# Z7_POWER2.net
KiCad netlist of a schematic drawn in Altium Designer
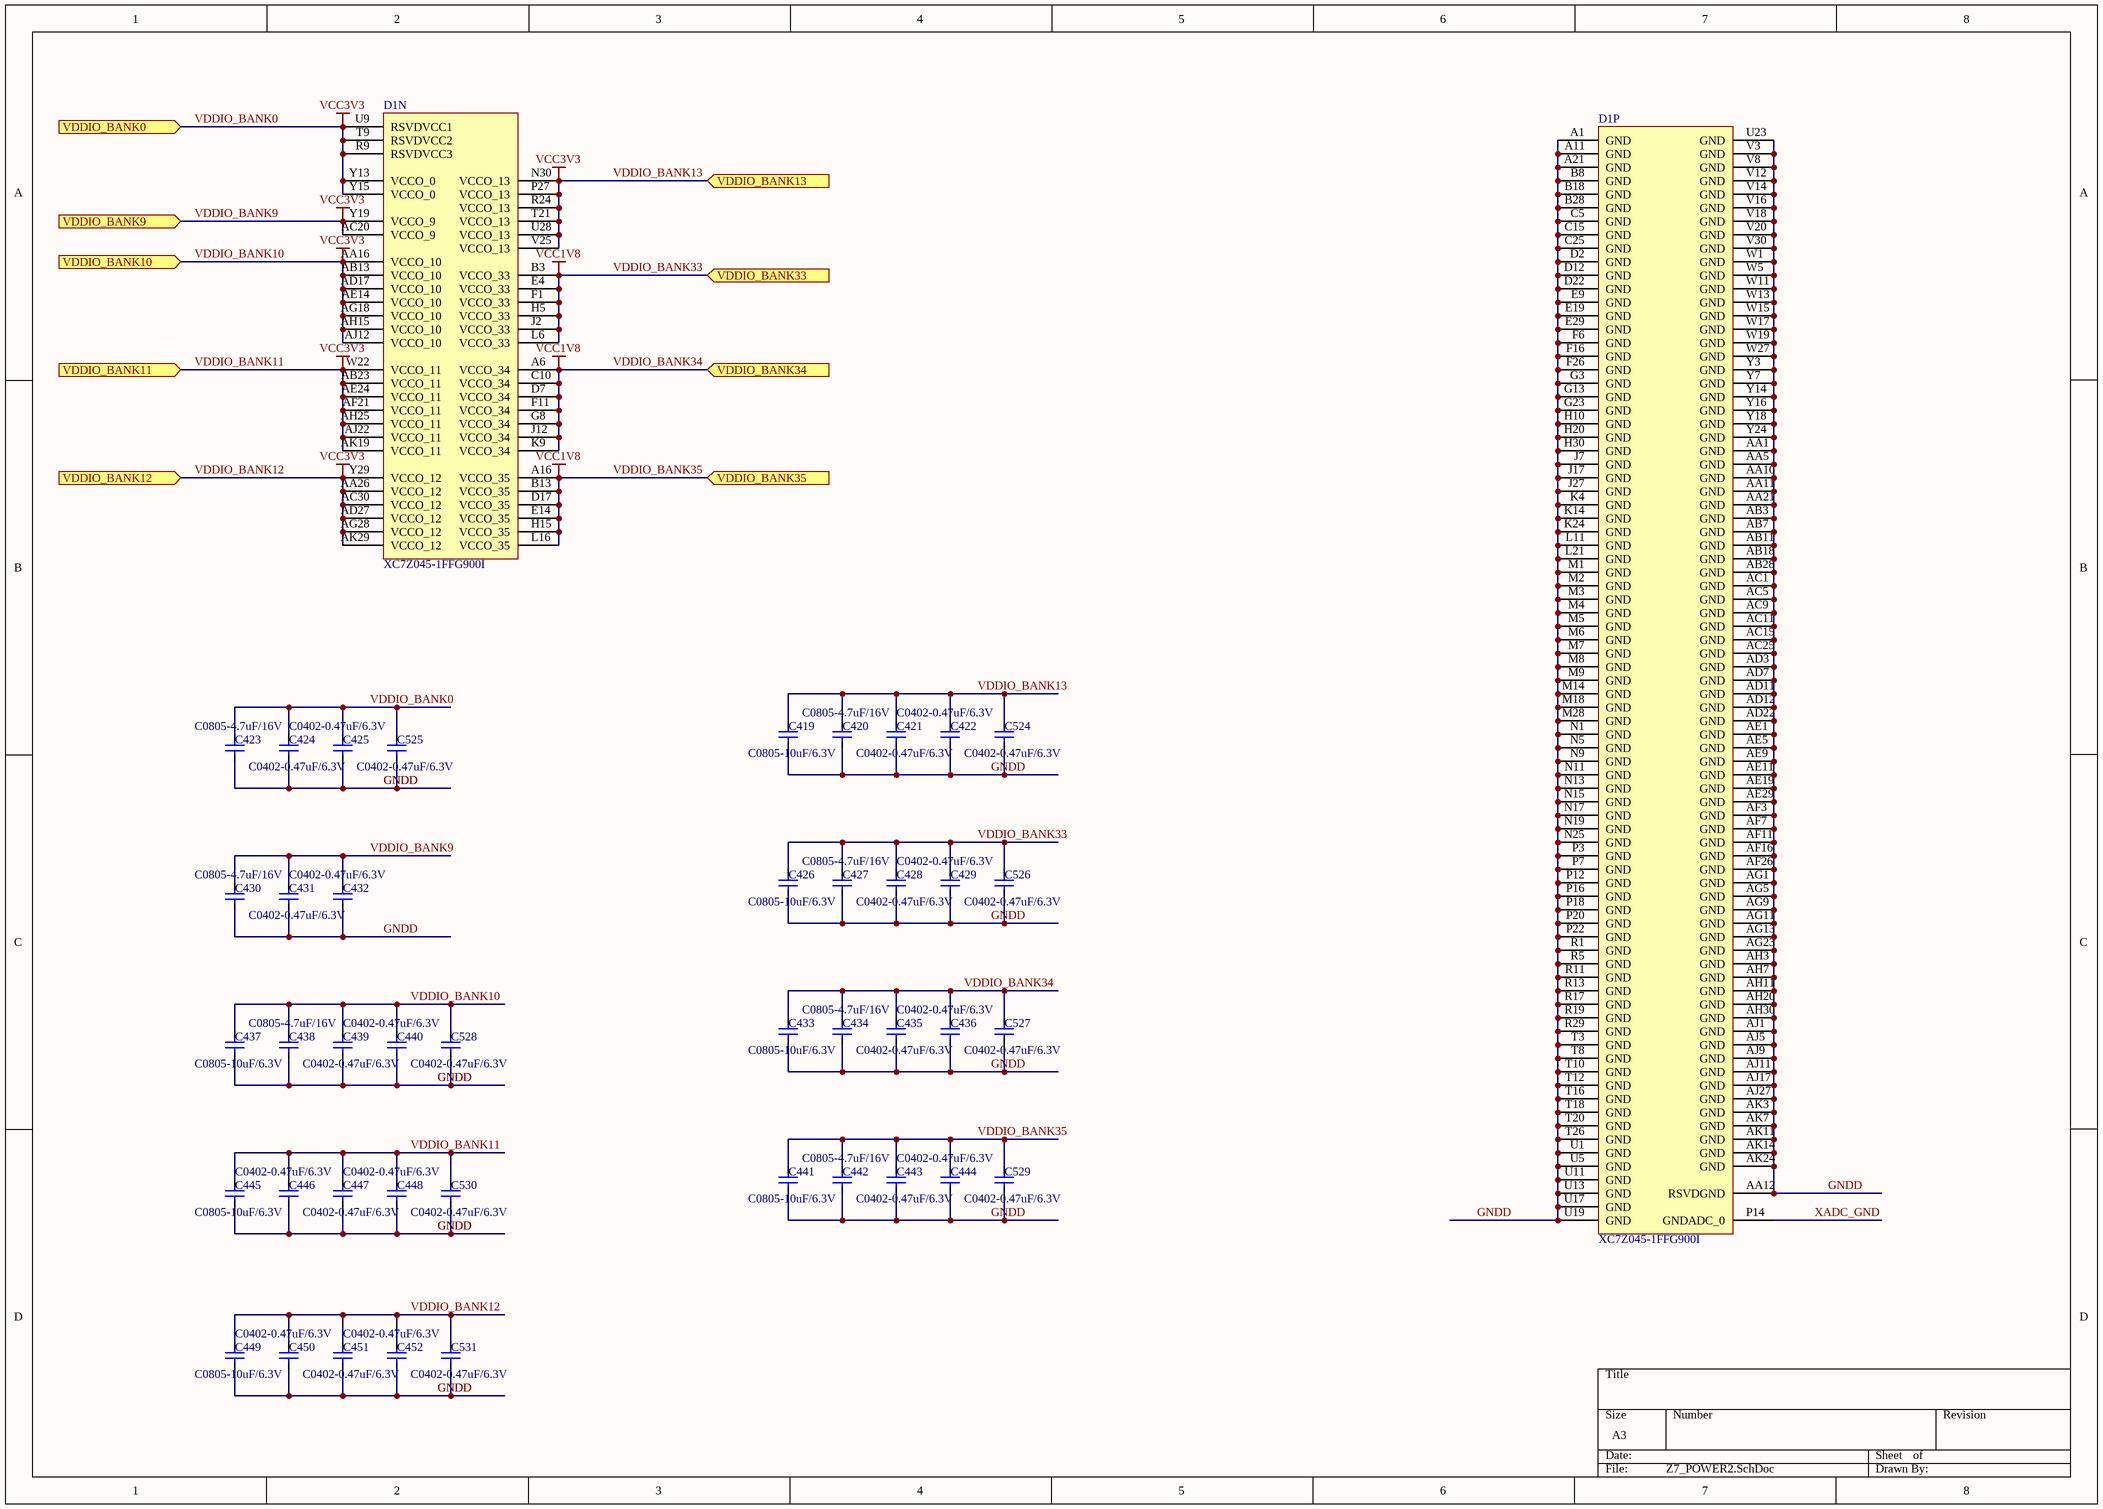
[diagram p0: Z7_POWER2.SchDoc]

(export (version "E")
  (design (tool "Eeschema 10.0.6"))
  (components
    (comp (ref "C419")
      (value "C0805-10uF/6.3V")
      (footprint "C0805")
      (fields (field (name "SCHEMATIC_PART") "CAP"))
      (libsource (lib "Database_Libs1") (part "CAP"))
    )
    (comp (ref "C420")
      (value "C0805-4.7uF/16V")
      (footprint "C0805")
      (description "X7R")
      (fields (field (name "SCHEMATIC_PART") "CAP") (field (name "MANUFACTURER") "SAMSUNG"))
      (libsource (lib "Database_Libs1") (part "CAP"))
    )
    (comp (ref "C421")
      (value "C0402-0.47uF/6.3V")
      (footprint "C0402")
      (description "X7R")
      (fields (field (name "SCHEMATIC_PART") "CAP") (field (name "MANUFACTURER") "SAMSUNG"))
      (libsource (lib "Database_Libs1") (part "CAP"))
    )
    (comp (ref "C422")
      (value "C0402-0.47uF/6.3V")
      (footprint "C0402")
      (description "X7R")
      (fields (field (name "SCHEMATIC_PART") "CAP") (field (name "MANUFACTURER") "SAMSUNG"))
      (libsource (lib "Database_Libs1") (part "CAP"))
    )
    (comp (ref "C423")
      (value "C0805-4.7uF/16V")
      (footprint "C0805")
      (description "X7R")
      (fields (field (name "SCHEMATIC_PART") "CAP") (field (name "MANUFACTURER") "SAMSUNG"))
      (libsource (lib "Database_Libs1") (part "CAP"))
    )
    (comp (ref "C424")
      (value "C0402-0.47uF/6.3V")
      (footprint "C0402")
      (description "X7R")
      (fields (field (name "SCHEMATIC_PART") "CAP") (field (name "MANUFACTURER") "SAMSUNG"))
      (libsource (lib "Database_Libs1") (part "CAP"))
    )
    (comp (ref "C425")
      (value "C0402-0.47uF/6.3V")
      (footprint "C0402")
      (description "X7R")
      (fields (field (name "SCHEMATIC_PART") "CAP") (field (name "MANUFACTURER") "SAMSUNG"))
      (libsource (lib "Database_Libs1") (part "CAP"))
    )
    (comp (ref "C426")
      (value "C0805-10uF/6.3V")
      (footprint "C0805")
      (fields (field (name "SCHEMATIC_PART") "CAP"))
      (libsource (lib "Database_Libs1") (part "CAP"))
    )
    (comp (ref "C427")
      (value "C0805-4.7uF/16V")
      (footprint "C0805")
      (description "X7R")
      (fields (field (name "SCHEMATIC_PART") "CAP") (field (name "MANUFACTURER") "SAMSUNG"))
      (libsource (lib "Database_Libs1") (part "CAP"))
    )
    (comp (ref "C428")
      (value "C0402-0.47uF/6.3V")
      (footprint "C0402")
      (description "X7R")
      (fields (field (name "SCHEMATIC_PART") "CAP") (field (name "MANUFACTURER") "SAMSUNG"))
      (libsource (lib "Database_Libs1") (part "CAP"))
    )
    (comp (ref "C429")
      (value "C0402-0.47uF/6.3V")
      (footprint "C0402")
      (description "X7R")
      (fields (field (name "SCHEMATIC_PART") "CAP") (field (name "MANUFACTURER") "SAMSUNG"))
      (libsource (lib "Database_Libs1") (part "CAP"))
    )
    (comp (ref "C430")
      (value "C0805-4.7uF/16V")
      (footprint "C0805")
      (description "X7R")
      (fields (field (name "SCHEMATIC_PART") "CAP") (field (name "MANUFACTURER") "SAMSUNG"))
      (libsource (lib "Database_Libs1") (part "CAP"))
    )
    (comp (ref "C431")
      (value "C0402-0.47uF/6.3V")
      (footprint "C0402")
      (description "X7R")
      (fields (field (name "SCHEMATIC_PART") "CAP") (field (name "MANUFACTURER") "SAMSUNG"))
      (libsource (lib "Database_Libs1") (part "CAP"))
    )
    (comp (ref "C432")
      (value "C0402-0.47uF/6.3V")
      (footprint "C0402")
      (description "X7R")
      (fields (field (name "SCHEMATIC_PART") "CAP") (field (name "MANUFACTURER") "SAMSUNG"))
      (libsource (lib "Database_Libs1") (part "CAP"))
    )
    (comp (ref "C433")
      (value "C0805-10uF/6.3V")
      (footprint "C0805")
      (fields (field (name "SCHEMATIC_PART") "CAP"))
      (libsource (lib "Database_Libs1") (part "CAP"))
    )
    (comp (ref "C434")
      (value "C0805-4.7uF/16V")
      (footprint "C0805")
      (description "X7R")
      (fields (field (name "SCHEMATIC_PART") "CAP") (field (name "MANUFACTURER") "SAMSUNG"))
      (libsource (lib "Database_Libs1") (part "CAP"))
    )
    (comp (ref "C435")
      (value "C0402-0.47uF/6.3V")
      (footprint "C0402")
      (description "X7R")
      (fields (field (name "SCHEMATIC_PART") "CAP") (field (name "MANUFACTURER") "SAMSUNG"))
      (libsource (lib "Database_Libs1") (part "CAP"))
    )
    (comp (ref "C436")
      (value "C0402-0.47uF/6.3V")
      (footprint "C0402")
      (description "X7R")
      (fields (field (name "SCHEMATIC_PART") "CAP") (field (name "MANUFACTURER") "SAMSUNG"))
      (libsource (lib "Database_Libs1") (part "CAP"))
    )
    (comp (ref "C437")
      (value "C0805-10uF/6.3V")
      (footprint "C0805")
      (fields (field (name "SCHEMATIC_PART") "CAP"))
      (libsource (lib "Database_Libs1") (part "CAP"))
    )
    (comp (ref "C438")
      (value "C0805-4.7uF/16V")
      (footprint "C0805")
      (description "X7R")
      (fields (field (name "SCHEMATIC_PART") "CAP") (field (name "MANUFACTURER") "SAMSUNG"))
      (libsource (lib "Database_Libs1") (part "CAP"))
    )
    (comp (ref "C439")
      (value "C0402-0.47uF/6.3V")
      (footprint "C0402")
      (description "X7R")
      (fields (field (name "SCHEMATIC_PART") "CAP") (field (name "MANUFACTURER") "SAMSUNG"))
      (libsource (lib "Database_Libs1") (part "CAP"))
    )
    (comp (ref "C440")
      (value "C0402-0.47uF/6.3V")
      (footprint "C0402")
      (description "X7R")
      (fields (field (name "SCHEMATIC_PART") "CAP") (field (name "MANUFACTURER") "SAMSUNG"))
      (libsource (lib "Database_Libs1") (part "CAP"))
    )
    (comp (ref "C441")
      (value "C0805-10uF/6.3V")
      (footprint "C0805")
      (fields (field (name "SCHEMATIC_PART") "CAP"))
      (libsource (lib "Database_Libs1") (part "CAP"))
    )
    (comp (ref "C442")
      (value "C0805-4.7uF/16V")
      (footprint "C0805")
      (description "X7R")
      (fields (field (name "SCHEMATIC_PART") "CAP") (field (name "MANUFACTURER") "SAMSUNG"))
      (libsource (lib "Database_Libs1") (part "CAP"))
    )
    (comp (ref "C443")
      (value "C0402-0.47uF/6.3V")
      (footprint "C0402")
      (description "X7R")
      (fields (field (name "SCHEMATIC_PART") "CAP") (field (name "MANUFACTURER") "SAMSUNG"))
      (libsource (lib "Database_Libs1") (part "CAP"))
    )
    (comp (ref "C444")
      (value "C0402-0.47uF/6.3V")
      (footprint "C0402")
      (description "X7R")
      (fields (field (name "SCHEMATIC_PART") "CAP") (field (name "MANUFACTURER") "SAMSUNG"))
      (libsource (lib "Database_Libs1") (part "CAP"))
    )
    (comp (ref "C445")
      (value "C0805-10uF/6.3V")
      (footprint "C0805")
      (fields (field (name "SCHEMATIC_PART") "CAP"))
      (libsource (lib "Database_Libs1") (part "CAP"))
    )
    (comp (ref "C446")
      (value "C0402-0.47uF/6.3V")
      (footprint "C0402")
      (description "X7R")
      (fields (field (name "SCHEMATIC_PART") "CAP") (field (name "MANUFACTURER") "SAMSUNG"))
      (libsource (lib "Database_Libs1") (part "CAP"))
    )
    (comp (ref "C447")
      (value "C0402-0.47uF/6.3V")
      (footprint "C0402")
      (description "X7R")
      (fields (field (name "SCHEMATIC_PART") "CAP") (field (name "MANUFACTURER") "SAMSUNG"))
      (libsource (lib "Database_Libs1") (part "CAP"))
    )
    (comp (ref "C448")
      (value "C0402-0.47uF/6.3V")
      (footprint "C0402")
      (description "X7R")
      (fields (field (name "SCHEMATIC_PART") "CAP") (field (name "MANUFACTURER") "SAMSUNG"))
      (libsource (lib "Database_Libs1") (part "CAP"))
    )
    (comp (ref "C449")
      (value "C0805-10uF/6.3V")
      (footprint "C0805")
      (fields (field (name "SCHEMATIC_PART") "CAP"))
      (libsource (lib "Database_Libs1") (part "CAP"))
    )
    (comp (ref "C450")
      (value "C0402-0.47uF/6.3V")
      (footprint "C0402")
      (description "X7R")
      (fields (field (name "SCHEMATIC_PART") "CAP") (field (name "MANUFACTURER") "SAMSUNG"))
      (libsource (lib "Database_Libs1") (part "CAP"))
    )
    (comp (ref "C451")
      (value "C0402-0.47uF/6.3V")
      (footprint "C0402")
      (description "X7R")
      (fields (field (name "SCHEMATIC_PART") "CAP") (field (name "MANUFACTURER") "SAMSUNG"))
      (libsource (lib "Database_Libs1") (part "CAP"))
    )
    (comp (ref "C452")
      (value "C0402-0.47uF/6.3V")
      (footprint "C0402")
      (description "X7R")
      (fields (field (name "SCHEMATIC_PART") "CAP") (field (name "MANUFACTURER") "SAMSUNG"))
      (libsource (lib "Database_Libs1") (part "CAP"))
    )
    (comp (ref "C524")
      (value "C0402-0.47uF/6.3V")
      (footprint "C0402")
      (description "X7R")
      (fields (field (name "SCHEMATIC_PART") "CAP") (field (name "MANUFACTURER") "SAMSUNG"))
      (libsource (lib "Database_Libs1") (part "CAP"))
    )
    (comp (ref "C525")
      (value "C0402-0.47uF/6.3V")
      (footprint "C0402")
      (description "X7R")
      (fields (field (name "SCHEMATIC_PART") "CAP") (field (name "MANUFACTURER") "SAMSUNG"))
      (libsource (lib "Database_Libs1") (part "CAP"))
    )
    (comp (ref "C526")
      (value "C0402-0.47uF/6.3V")
      (footprint "C0402")
      (description "X7R")
      (fields (field (name "SCHEMATIC_PART") "CAP") (field (name "MANUFACTURER") "SAMSUNG"))
      (libsource (lib "Database_Libs1") (part "CAP"))
    )
    (comp (ref "C527")
      (value "C0402-0.47uF/6.3V")
      (footprint "C0402")
      (description "X7R")
      (fields (field (name "SCHEMATIC_PART") "CAP") (field (name "MANUFACTURER") "SAMSUNG"))
      (libsource (lib "Database_Libs1") (part "CAP"))
    )
    (comp (ref "C528")
      (value "C0402-0.47uF/6.3V")
      (footprint "C0402")
      (description "X7R")
      (fields (field (name "SCHEMATIC_PART") "CAP") (field (name "MANUFACTURER") "SAMSUNG"))
      (libsource (lib "Database_Libs1") (part "CAP"))
    )
    (comp (ref "C529")
      (value "C0402-0.47uF/6.3V")
      (footprint "C0402")
      (description "X7R")
      (fields (field (name "SCHEMATIC_PART") "CAP") (field (name "MANUFACTURER") "SAMSUNG"))
      (libsource (lib "Database_Libs1") (part "CAP"))
    )
    (comp (ref "C530")
      (value "C0402-0.47uF/6.3V")
      (footprint "C0402")
      (description "X7R")
      (fields (field (name "SCHEMATIC_PART") "CAP") (field (name "MANUFACTURER") "SAMSUNG"))
      (libsource (lib "Database_Libs1") (part "CAP"))
    )
    (comp (ref "C531")
      (value "C0402-0.47uF/6.3V")
      (footprint "C0402")
      (description "X7R")
      (fields (field (name "SCHEMATIC_PART") "CAP") (field (name "MANUFACTURER") "SAMSUNG"))
      (libsource (lib "Database_Libs1") (part "CAP"))
    )
    (comp (ref "D1")
      (value "XC7Z045-1FFG900I")
      (footprint "FFG900")
      (fields (field (name "GENERIC PART NUMBER") "XC7Z045") (field (name "MANUFACTURER") "Xilinx"))
      (libsource (lib "Xilinx Zynq-7000") (part "XC7Z045-1FFG900I"))
    )
  )
  (nets
    (net (code "1") (name "/GNDD") (class "Default")
      (node (ref "C419") (pin "2") (pinfunction "2_2") (pintype "passive"))
      (node (ref "C420") (pin "2") (pinfunction "2_2") (pintype "passive"))
      (node (ref "C421") (pin "2") (pinfunction "2_2") (pintype "passive"))
      (node (ref "C422") (pin "2") (pinfunction "2_2") (pintype "passive"))
      (node (ref "C423") (pin "2") (pinfunction "2_2") (pintype "passive"))
      (node (ref "C424") (pin "2") (pinfunction "2_2") (pintype "passive"))
      (node (ref "C425") (pin "2") (pinfunction "2_2") (pintype "passive"))
      (node (ref "C426") (pin "2") (pinfunction "2_2") (pintype "passive"))
      (node (ref "C427") (pin "2") (pinfunction "2_2") (pintype "passive"))
      (node (ref "C428") (pin "2") (pinfunction "2_2") (pintype "passive"))
      (node (ref "C429") (pin "2") (pinfunction "2_2") (pintype "passive"))
      (node (ref "C430") (pin "2") (pinfunction "2_2") (pintype "passive"))
      (node (ref "C431") (pin "2") (pinfunction "2_2") (pintype "passive"))
      (node (ref "C432") (pin "2") (pinfunction "2_2") (pintype "passive"))
      (node (ref "C433") (pin "2") (pinfunction "2_2") (pintype "passive"))
      (node (ref "C434") (pin "2") (pinfunction "2_2") (pintype "passive"))
      (node (ref "C435") (pin "2") (pinfunction "2_2") (pintype "passive"))
      (node (ref "C436") (pin "2") (pinfunction "2_2") (pintype "passive"))
      (node (ref "C437") (pin "2") (pinfunction "2_2") (pintype "passive"))
      (node (ref "C438") (pin "2") (pinfunction "2_2") (pintype "passive"))
      (node (ref "C439") (pin "2") (pinfunction "2_2") (pintype "passive"))
      (node (ref "C440") (pin "2") (pinfunction "2_2") (pintype "passive"))
      (node (ref "C441") (pin "2") (pinfunction "2_2") (pintype "passive"))
      (node (ref "C442") (pin "2") (pinfunction "2_2") (pintype "passive"))
      (node (ref "C443") (pin "2") (pinfunction "2_2") (pintype "passive"))
      (node (ref "C444") (pin "2") (pinfunction "2_2") (pintype "passive"))
      (node (ref "C445") (pin "2") (pinfunction "2_2") (pintype "passive"))
      (node (ref "C446") (pin "2") (pinfunction "2_2") (pintype "passive"))
      (node (ref "C447") (pin "2") (pinfunction "2_2") (pintype "passive"))
      (node (ref "C448") (pin "2") (pinfunction "2_2") (pintype "passive"))
      (node (ref "C449") (pin "2") (pinfunction "2_2") (pintype "passive"))
      (node (ref "C450") (pin "2") (pinfunction "2_2") (pintype "passive"))
      (node (ref "C451") (pin "2") (pinfunction "2_2") (pintype "passive"))
      (node (ref "C452") (pin "2") (pinfunction "2_2") (pintype "passive"))
      (node (ref "C524") (pin "2") (pinfunction "2_2") (pintype "passive"))
      (node (ref "C525") (pin "2") (pinfunction "2_2") (pintype "passive"))
      (node (ref "C526") (pin "2") (pinfunction "2_2") (pintype "passive"))
      (node (ref "C527") (pin "2") (pinfunction "2_2") (pintype "passive"))
      (node (ref "C528") (pin "2") (pinfunction "2_2") (pintype "passive"))
      (node (ref "C529") (pin "2") (pinfunction "2_2") (pintype "passive"))
      (node (ref "C530") (pin "2") (pinfunction "2_2") (pintype "passive"))
      (node (ref "C531") (pin "2") (pinfunction "2_2") (pintype "passive"))
      (node (ref "D1") (pin "A1") (pinfunction "GND_A1") (pintype "power_in"))
      (node (ref "D1") (pin "A11") (pinfunction "GND_A11") (pintype "power_in"))
      (node (ref "D1") (pin "A21") (pinfunction "GND_A21") (pintype "power_in"))
      (node (ref "D1") (pin "AA1") (pinfunction "GND_AA1") (pintype "power_in"))
      (node (ref "D1") (pin "AA10") (pinfunction "GND_AA10") (pintype "power_in"))
      (node (ref "D1") (pin "AA11") (pinfunction "GND_AA11") (pintype "power_in"))
      (node (ref "D1") (pin "AA12") (pinfunction "RSVDGND_AA12") (pintype "power_in"))
      (node (ref "D1") (pin "AA21") (pinfunction "GND_AA21") (pintype "power_in"))
      (node (ref "D1") (pin "AA5") (pinfunction "GND_AA5") (pintype "power_in"))
      (node (ref "D1") (pin "AB11") (pinfunction "GND_AB11") (pintype "power_in"))
      (node (ref "D1") (pin "AB18") (pinfunction "GND_AB18") (pintype "power_in"))
      (node (ref "D1") (pin "AB28") (pinfunction "GND_AB28") (pintype "power_in"))
      (node (ref "D1") (pin "AB3") (pinfunction "GND_AB3") (pintype "power_in"))
      (node (ref "D1") (pin "AB7") (pinfunction "GND_AB7") (pintype "power_in"))
      (node (ref "D1") (pin "AC1") (pinfunction "GND_AC1") (pintype "power_in"))
      (node (ref "D1") (pin "AC11") (pinfunction "GND_AC11") (pintype "power_in"))
      (node (ref "D1") (pin "AC15") (pinfunction "GND_AC15") (pintype "power_in"))
      (node (ref "D1") (pin "AC25") (pinfunction "GND_AC25") (pintype "power_in"))
      (node (ref "D1") (pin "AC5") (pinfunction "GND_AC5") (pintype "power_in"))
      (node (ref "D1") (pin "AC9") (pinfunction "GND_AC9") (pintype "power_in"))
      (node (ref "D1") (pin "AD11") (pinfunction "GND_AD11") (pintype "power_in"))
      (node (ref "D1") (pin "AD12") (pinfunction "GND_AD12") (pintype "power_in"))
      (node (ref "D1") (pin "AD22") (pinfunction "GND_AD22") (pintype "power_in"))
      (node (ref "D1") (pin "AD3") (pinfunction "GND_AD3") (pintype "power_in"))
      (node (ref "D1") (pin "AD7") (pinfunction "GND_AD7") (pintype "power_in"))
      (node (ref "D1") (pin "AE1") (pinfunction "GND_AE1") (pintype "power_in"))
      (node (ref "D1") (pin "AE11") (pinfunction "GND_AE11") (pintype "power_in"))
      (node (ref "D1") (pin "AE19") (pinfunction "GND_AE19") (pintype "power_in"))
      (node (ref "D1") (pin "AE29") (pinfunction "GND_AE29") (pintype "power_in"))
      (node (ref "D1") (pin "AE5") (pinfunction "GND_AE5") (pintype "power_in"))
      (node (ref "D1") (pin "AE9") (pinfunction "GND_AE9") (pintype "power_in"))
      (node (ref "D1") (pin "AF11") (pinfunction "GND_AF11") (pintype "power_in"))
      (node (ref "D1") (pin "AF16") (pinfunction "GND_AF16") (pintype "power_in"))
      (node (ref "D1") (pin "AF26") (pinfunction "GND_AF26") (pintype "power_in"))
      (node (ref "D1") (pin "AF3") (pinfunction "GND_AF3") (pintype "power_in"))
      (node (ref "D1") (pin "AF7") (pinfunction "GND_AF7") (pintype "power_in"))
      (node (ref "D1") (pin "AG1") (pinfunction "GND_AG1") (pintype "power_in"))
      (node (ref "D1") (pin "AG11") (pinfunction "GND_AG11") (pintype "power_in"))
      (node (ref "D1") (pin "AG13") (pinfunction "GND_AG13") (pintype "power_in"))
      (node (ref "D1") (pin "AG23") (pinfunction "GND_AG23") (pintype "power_in"))
      (node (ref "D1") (pin "AG5") (pinfunction "GND_AG5") (pintype "power_in"))
      (node (ref "D1") (pin "AG9") (pinfunction "GND_AG9") (pintype "power_in"))
      (node (ref "D1") (pin "AH11") (pinfunction "GND_AH11") (pintype "power_in"))
      (node (ref "D1") (pin "AH20") (pinfunction "GND_AH20") (pintype "power_in"))
      (node (ref "D1") (pin "AH3") (pinfunction "GND_AH3") (pintype "power_in"))
      (node (ref "D1") (pin "AH30") (pinfunction "GND_AH30") (pintype "power_in"))
      (node (ref "D1") (pin "AH7") (pinfunction "GND_AH7") (pintype "power_in"))
      (node (ref "D1") (pin "AJ1") (pinfunction "GND_AJ1") (pintype "power_in"))
      (node (ref "D1") (pin "AJ11") (pinfunction "GND_AJ11") (pintype "power_in"))
      (node (ref "D1") (pin "AJ17") (pinfunction "GND_AJ17") (pintype "power_in"))
      (node (ref "D1") (pin "AJ27") (pinfunction "GND_AJ27") (pintype "power_in"))
      (node (ref "D1") (pin "AJ5") (pinfunction "GND_AJ5") (pintype "power_in"))
      (node (ref "D1") (pin "AJ9") (pinfunction "GND_AJ9") (pintype "power_in"))
      (node (ref "D1") (pin "AK11") (pinfunction "GND_AK11") (pintype "power_in"))
      (node (ref "D1") (pin "AK14") (pinfunction "GND_AK14") (pintype "power_in"))
      (node (ref "D1") (pin "AK24") (pinfunction "GND_AK24") (pintype "power_in"))
      (node (ref "D1") (pin "AK3") (pinfunction "GND_AK3") (pintype "power_in"))
      (node (ref "D1") (pin "AK7") (pinfunction "GND_AK7") (pintype "power_in"))
      (node (ref "D1") (pin "B18") (pinfunction "GND_B18") (pintype "power_in"))
      (node (ref "D1") (pin "B28") (pinfunction "GND_B28") (pintype "power_in"))
      (node (ref "D1") (pin "B8") (pinfunction "GND_B8") (pintype "power_in"))
      (node (ref "D1") (pin "C15") (pinfunction "GND_C15") (pintype "power_in"))
      (node (ref "D1") (pin "C25") (pinfunction "GND_C25") (pintype "power_in"))
      (node (ref "D1") (pin "C5") (pinfunction "GND_C5") (pintype "power_in"))
      (node (ref "D1") (pin "D12") (pinfunction "GND_D12") (pintype "power_in"))
      (node (ref "D1") (pin "D2") (pinfunction "GND_D2") (pintype "power_in"))
      (node (ref "D1") (pin "D22") (pinfunction "GND_D22") (pintype "power_in"))
      (node (ref "D1") (pin "E19") (pinfunction "GND_E19") (pintype "power_in"))
      (node (ref "D1") (pin "E29") (pinfunction "GND_E29") (pintype "power_in"))
      (node (ref "D1") (pin "E9") (pinfunction "GND_E9") (pintype "power_in"))
      (node (ref "D1") (pin "F16") (pinfunction "GND_F16") (pintype "power_in"))
      (node (ref "D1") (pin "F26") (pinfunction "GND_F26") (pintype "power_in"))
      (node (ref "D1") (pin "F6") (pinfunction "GND_F6") (pintype "power_in"))
      (node (ref "D1") (pin "G13") (pinfunction "GND_G13") (pintype "power_in"))
      (node (ref "D1") (pin "G23") (pinfunction "GND_G23") (pintype "power_in"))
      (node (ref "D1") (pin "G3") (pinfunction "GND_G3") (pintype "power_in"))
      (node (ref "D1") (pin "H10") (pinfunction "GND_H10") (pintype "power_in"))
      (node (ref "D1") (pin "H20") (pinfunction "GND_H20") (pintype "power_in"))
      (node (ref "D1") (pin "H30") (pinfunction "GND_H30") (pintype "power_in"))
      (node (ref "D1") (pin "J17") (pinfunction "GND_J17") (pintype "power_in"))
      (node (ref "D1") (pin "J27") (pinfunction "GND_J27") (pintype "power_in"))
      (node (ref "D1") (pin "J7") (pinfunction "GND_J7") (pintype "power_in"))
      (node (ref "D1") (pin "K14") (pinfunction "GND_K14") (pintype "power_in"))
      (node (ref "D1") (pin "K24") (pinfunction "GND_K24") (pintype "power_in"))
      (node (ref "D1") (pin "K4") (pinfunction "GND_K4") (pintype "power_in"))
      (node (ref "D1") (pin "L11") (pinfunction "GND_L11") (pintype "power_in"))
      (node (ref "D1") (pin "L21") (pinfunction "GND_L21") (pintype "power_in"))
      (node (ref "D1") (pin "M1") (pinfunction "GND_M1") (pintype "power_in"))
      (node (ref "D1") (pin "M14") (pinfunction "GND_M14") (pintype "power_in"))
      (node (ref "D1") (pin "M18") (pinfunction "GND_M18") (pintype "power_in"))
      (node (ref "D1") (pin "M2") (pinfunction "GND_M2") (pintype "power_in"))
      (node (ref "D1") (pin "M28") (pinfunction "GND_M28") (pintype "power_in"))
      (node (ref "D1") (pin "M3") (pinfunction "GND_M3") (pintype "power_in"))
      (node (ref "D1") (pin "M4") (pinfunction "GND_M4") (pintype "power_in"))
      (node (ref "D1") (pin "M5") (pinfunction "GND_M5") (pintype "power_in"))
      (node (ref "D1") (pin "M6") (pinfunction "GND_M6") (pintype "power_in"))
      (node (ref "D1") (pin "M7") (pinfunction "GND_M7") (pintype "power_in"))
      (node (ref "D1") (pin "M8") (pinfunction "GND_M8") (pintype "power_in"))
      (node (ref "D1") (pin "M9") (pinfunction "GND_M9") (pintype "power_in"))
      (node (ref "D1") (pin "N1") (pinfunction "GND_N1") (pintype "power_in"))
      (node (ref "D1") (pin "N11") (pinfunction "GND_N11") (pintype "power_in"))
      (node (ref "D1") (pin "N13") (pinfunction "GND_N13") (pintype "power_in"))
      (node (ref "D1") (pin "N15") (pinfunction "GND_N15") (pintype "power_in"))
      (node (ref "D1") (pin "N17") (pinfunction "GND_N17") (pintype "power_in"))
      (node (ref "D1") (pin "N19") (pinfunction "GND_N19") (pintype "power_in"))
      (node (ref "D1") (pin "N25") (pinfunction "GND_N25") (pintype "power_in"))
      (node (ref "D1") (pin "N5") (pinfunction "GND_N5") (pintype "power_in"))
      (node (ref "D1") (pin "N9") (pinfunction "GND_N9") (pintype "power_in"))
      (node (ref "D1") (pin "P12") (pinfunction "GND_P12") (pintype "power_in"))
      (node (ref "D1") (pin "P16") (pinfunction "GND_P16") (pintype "power_in"))
      (node (ref "D1") (pin "P18") (pinfunction "GND_P18") (pintype "power_in"))
      (node (ref "D1") (pin "P20") (pinfunction "GND_P20") (pintype "power_in"))
      (node (ref "D1") (pin "P22") (pinfunction "GND_P22") (pintype "power_in"))
      (node (ref "D1") (pin "P3") (pinfunction "GND_P3") (pintype "power_in"))
      (node (ref "D1") (pin "P7") (pinfunction "GND_P7") (pintype "power_in"))
      (node (ref "D1") (pin "R1") (pinfunction "GND_R1") (pintype "power_in"))
      (node (ref "D1") (pin "R11") (pinfunction "GND_R11") (pintype "power_in"))
      (node (ref "D1") (pin "R13") (pinfunction "GND_R13") (pintype "power_in"))
      (node (ref "D1") (pin "R17") (pinfunction "GND_R17") (pintype "power_in"))
      (node (ref "D1") (pin "R19") (pinfunction "GND_R19") (pintype "power_in"))
      (node (ref "D1") (pin "R29") (pinfunction "GND_R29") (pintype "power_in"))
      (node (ref "D1") (pin "R5") (pinfunction "GND_R5") (pintype "power_in"))
      (node (ref "D1") (pin "T10") (pinfunction "GND_T10") (pintype "power_in"))
      (node (ref "D1") (pin "T12") (pinfunction "GND_T12") (pintype "power_in"))
      (node (ref "D1") (pin "T16") (pinfunction "GND_T16") (pintype "power_in"))
      (node (ref "D1") (pin "T18") (pinfunction "GND_T18") (pintype "power_in"))
      (node (ref "D1") (pin "T20") (pinfunction "GND_T20") (pintype "power_in"))
      (node (ref "D1") (pin "T26") (pinfunction "GND_T26") (pintype "power_in"))
      (node (ref "D1") (pin "T3") (pinfunction "GND_T3") (pintype "power_in"))
      (node (ref "D1") (pin "T8") (pinfunction "GND_T8") (pintype "power_in"))
      (node (ref "D1") (pin "U1") (pinfunction "GND_U1") (pintype "power_in"))
      (node (ref "D1") (pin "U11") (pinfunction "GND_U11") (pintype "power_in"))
      (node (ref "D1") (pin "U13") (pinfunction "GND_U13") (pintype "power_in"))
      (node (ref "D1") (pin "U17") (pinfunction "GND_U17") (pintype "power_in"))
      (node (ref "D1") (pin "U19") (pinfunction "GND_U19") (pintype "power_in"))
      (node (ref "D1") (pin "U23") (pinfunction "GND_U23") (pintype "power_in"))
      (node (ref "D1") (pin "U5") (pinfunction "GND_U5") (pintype "power_in"))
      (node (ref "D1") (pin "V12") (pinfunction "GND_V12") (pintype "power_in"))
      (node (ref "D1") (pin "V14") (pinfunction "GND_V14") (pintype "power_in"))
      (node (ref "D1") (pin "V16") (pinfunction "GND_V16") (pintype "power_in"))
      (node (ref "D1") (pin "V18") (pinfunction "GND_V18") (pintype "power_in"))
      (node (ref "D1") (pin "V20") (pinfunction "GND_V20") (pintype "power_in"))
      (node (ref "D1") (pin "V3") (pinfunction "GND_V3") (pintype "power_in"))
      (node (ref "D1") (pin "V30") (pinfunction "GND_V30") (pintype "power_in"))
      (node (ref "D1") (pin "V8") (pinfunction "GND_V8") (pintype "power_in"))
      (node (ref "D1") (pin "W1") (pinfunction "GND_W1") (pintype "power_in"))
      (node (ref "D1") (pin "W11") (pinfunction "GND_W11") (pintype "power_in"))
      (node (ref "D1") (pin "W13") (pinfunction "GND_W13") (pintype "power_in"))
      (node (ref "D1") (pin "W15") (pinfunction "GND_W15") (pintype "power_in"))
      (node (ref "D1") (pin "W17") (pinfunction "GND_W17") (pintype "power_in"))
      (node (ref "D1") (pin "W19") (pinfunction "GND_W19") (pintype "power_in"))
      (node (ref "D1") (pin "W27") (pinfunction "GND_W27") (pintype "power_in"))
      (node (ref "D1") (pin "W5") (pinfunction "GND_W5") (pintype "power_in"))
      (node (ref "D1") (pin "Y14") (pinfunction "GND_Y14") (pintype "power_in"))
      (node (ref "D1") (pin "Y16") (pinfunction "GND_Y16") (pintype "power_in"))
      (node (ref "D1") (pin "Y18") (pinfunction "GND_Y18") (pintype "power_in"))
      (node (ref "D1") (pin "Y24") (pinfunction "GND_Y24") (pintype "power_in"))
      (node (ref "D1") (pin "Y3") (pinfunction "GND_Y3") (pintype "power_in"))
      (node (ref "D1") (pin "Y7") (pinfunction "GND_Y7") (pintype "power_in"))
    )
    (net (code "2") (name "/XADC_GND") (class "Default")
      (node (ref "D1") (pin "P14") (pinfunction "GNDADC_0_P14") (pintype "power_in"))
    )
    (net (code "3") (name "VCC1V8") (class "Default")
      (node (ref "C426") (pin "1") (pinfunction "1_1") (pintype "passive"))
      (node (ref "C427") (pin "1") (pinfunction "1_1") (pintype "passive"))
      (node (ref "C428") (pin "1") (pinfunction "1_1") (pintype "passive"))
      (node (ref "C429") (pin "1") (pinfunction "1_1") (pintype "passive"))
      (node (ref "C433") (pin "1") (pinfunction "1_1") (pintype "passive"))
      (node (ref "C434") (pin "1") (pinfunction "1_1") (pintype "passive"))
      (node (ref "C435") (pin "1") (pinfunction "1_1") (pintype "passive"))
      (node (ref "C436") (pin "1") (pinfunction "1_1") (pintype "passive"))
      (node (ref "C441") (pin "1") (pinfunction "1_1") (pintype "passive"))
      (node (ref "C442") (pin "1") (pinfunction "1_1") (pintype "passive"))
      (node (ref "C443") (pin "1") (pinfunction "1_1") (pintype "passive"))
      (node (ref "C444") (pin "1") (pinfunction "1_1") (pintype "passive"))
      (node (ref "C526") (pin "1") (pinfunction "1_1") (pintype "passive"))
      (node (ref "C527") (pin "1") (pinfunction "1_1") (pintype "passive"))
      (node (ref "C529") (pin "1") (pinfunction "1_1") (pintype "passive"))
      (node (ref "D1") (pin "A16") (pinfunction "VCCO_35_A16") (pintype "power_in"))
      (node (ref "D1") (pin "A6") (pinfunction "VCCO_34_A6") (pintype "power_in"))
      (node (ref "D1") (pin "B13") (pinfunction "VCCO_35_B13") (pintype "power_in"))
      (node (ref "D1") (pin "B3") (pinfunction "VCCO_33_B3") (pintype "power_in"))
      (node (ref "D1") (pin "C10") (pinfunction "VCCO_34_C10") (pintype "power_in"))
      (node (ref "D1") (pin "D17") (pinfunction "VCCO_35_D17") (pintype "power_in"))
      (node (ref "D1") (pin "D7") (pinfunction "VCCO_34_D7") (pintype "power_in"))
      (node (ref "D1") (pin "E14") (pinfunction "VCCO_35_E14") (pintype "power_in"))
      (node (ref "D1") (pin "E4") (pinfunction "VCCO_33_E4") (pintype "power_in"))
      (node (ref "D1") (pin "F1") (pinfunction "VCCO_33_F1") (pintype "power_in"))
      (node (ref "D1") (pin "F11") (pinfunction "VCCO_34_F11") (pintype "power_in"))
      (node (ref "D1") (pin "G8") (pinfunction "VCCO_34_G8") (pintype "power_in"))
      (node (ref "D1") (pin "H15") (pinfunction "VCCO_35_H15") (pintype "power_in"))
      (node (ref "D1") (pin "H5") (pinfunction "VCCO_33_H5") (pintype "power_in"))
      (node (ref "D1") (pin "J12") (pinfunction "VCCO_34_J12") (pintype "power_in"))
      (node (ref "D1") (pin "J2") (pinfunction "VCCO_33_J2") (pintype "power_in"))
      (node (ref "D1") (pin "K9") (pinfunction "VCCO_34_K9") (pintype "power_in"))
      (node (ref "D1") (pin "L16") (pinfunction "VCCO_35_L16") (pintype "power_in"))
      (node (ref "D1") (pin "L6") (pinfunction "VCCO_33_L6") (pintype "power_in"))
    )
    (net (code "4") (name "VCC3V3") (class "Default")
      (node (ref "C419") (pin "1") (pinfunction "1_1") (pintype "passive"))
      (node (ref "C420") (pin "1") (pinfunction "1_1") (pintype "passive"))
      (node (ref "C421") (pin "1") (pinfunction "1_1") (pintype "passive"))
      (node (ref "C422") (pin "1") (pinfunction "1_1") (pintype "passive"))
      (node (ref "C423") (pin "1") (pinfunction "1_1") (pintype "passive"))
      (node (ref "C424") (pin "1") (pinfunction "1_1") (pintype "passive"))
      (node (ref "C425") (pin "1") (pinfunction "1_1") (pintype "passive"))
      (node (ref "C430") (pin "1") (pinfunction "1_1") (pintype "passive"))
      (node (ref "C431") (pin "1") (pinfunction "1_1") (pintype "passive"))
      (node (ref "C432") (pin "1") (pinfunction "1_1") (pintype "passive"))
      (node (ref "C437") (pin "1") (pinfunction "1_1") (pintype "passive"))
      (node (ref "C438") (pin "1") (pinfunction "1_1") (pintype "passive"))
      (node (ref "C439") (pin "1") (pinfunction "1_1") (pintype "passive"))
      (node (ref "C440") (pin "1") (pinfunction "1_1") (pintype "passive"))
      (node (ref "C445") (pin "1") (pinfunction "1_1") (pintype "passive"))
      (node (ref "C446") (pin "1") (pinfunction "1_1") (pintype "passive"))
      (node (ref "C447") (pin "1") (pinfunction "1_1") (pintype "passive"))
      (node (ref "C448") (pin "1") (pinfunction "1_1") (pintype "passive"))
      (node (ref "C449") (pin "1") (pinfunction "1_1") (pintype "passive"))
      (node (ref "C450") (pin "1") (pinfunction "1_1") (pintype "passive"))
      (node (ref "C451") (pin "1") (pinfunction "1_1") (pintype "passive"))
      (node (ref "C452") (pin "1") (pinfunction "1_1") (pintype "passive"))
      (node (ref "C524") (pin "1") (pinfunction "1_1") (pintype "passive"))
      (node (ref "C525") (pin "1") (pinfunction "1_1") (pintype "passive"))
      (node (ref "C528") (pin "1") (pinfunction "1_1") (pintype "passive"))
      (node (ref "C530") (pin "1") (pinfunction "1_1") (pintype "passive"))
      (node (ref "C531") (pin "1") (pinfunction "1_1") (pintype "passive"))
      (node (ref "D1") (pin "AA16") (pinfunction "VCCO_10_AA16") (pintype "power_in"))
      (node (ref "D1") (pin "AA26") (pinfunction "VCCO_12_AA26") (pintype "power_in"))
      (node (ref "D1") (pin "AB13") (pinfunction "VCCO_10_AB13") (pintype "power_in"))
      (node (ref "D1") (pin "AB23") (pinfunction "VCCO_11_AB23") (pintype "power_in"))
      (node (ref "D1") (pin "AC20") (pinfunction "VCCO_9_AC20") (pintype "power_in"))
      (node (ref "D1") (pin "AC30") (pinfunction "VCCO_12_AC30") (pintype "power_in"))
      (node (ref "D1") (pin "AD17") (pinfunction "VCCO_10_AD17") (pintype "power_in"))
      (node (ref "D1") (pin "AD27") (pinfunction "VCCO_12_AD27") (pintype "power_in"))
      (node (ref "D1") (pin "AE14") (pinfunction "VCCO_10_AE14") (pintype "power_in"))
      (node (ref "D1") (pin "AE24") (pinfunction "VCCO_11_AE24") (pintype "power_in"))
      (node (ref "D1") (pin "AF21") (pinfunction "VCCO_11_AF21") (pintype "power_in"))
      (node (ref "D1") (pin "AG18") (pinfunction "VCCO_10_AG18") (pintype "power_in"))
      (node (ref "D1") (pin "AG28") (pinfunction "VCCO_12_AG28") (pintype "power_in"))
      (node (ref "D1") (pin "AH15") (pinfunction "VCCO_10_AH15") (pintype "power_in"))
      (node (ref "D1") (pin "AH25") (pinfunction "VCCO_11_AH25") (pintype "power_in"))
      (node (ref "D1") (pin "AJ12") (pinfunction "VCCO_10_AJ12") (pintype "power_in"))
      (node (ref "D1") (pin "AJ22") (pinfunction "VCCO_11_AJ22") (pintype "power_in"))
      (node (ref "D1") (pin "AK19") (pinfunction "VCCO_11_AK19") (pintype "power_in"))
      (node (ref "D1") (pin "AK29") (pinfunction "VCCO_12_AK29") (pintype "power_in"))
      (node (ref "D1") (pin "N30") (pinfunction "VCCO_13_N30") (pintype "power_in"))
      (node (ref "D1") (pin "P27") (pinfunction "VCCO_13_P27") (pintype "power_in"))
      (node (ref "D1") (pin "R24") (pinfunction "VCCO_13_R24") (pintype "power_in"))
      (node (ref "D1") (pin "R9") (pinfunction "RSVDVCC3_R9") (pintype "power_in"))
      (node (ref "D1") (pin "T21") (pinfunction "VCCO_13_T21") (pintype "power_in"))
      (node (ref "D1") (pin "T9") (pinfunction "RSVDVCC2_T9") (pintype "power_in"))
      (node (ref "D1") (pin "U28") (pinfunction "VCCO_13_U28") (pintype "power_in"))
      (node (ref "D1") (pin "U9") (pinfunction "RSVDVCC1_U9") (pintype "power_in"))
      (node (ref "D1") (pin "V25") (pinfunction "VCCO_13_V25") (pintype "power_in"))
      (node (ref "D1") (pin "W22") (pinfunction "VCCO_11_W22") (pintype "power_in"))
      (node (ref "D1") (pin "Y13") (pinfunction "VCCO_0_Y13") (pintype "power_in"))
      (node (ref "D1") (pin "Y15") (pinfunction "VCCO_0_Y15") (pintype "power_in"))
      (node (ref "D1") (pin "Y19") (pinfunction "VCCO_9_Y19") (pintype "power_in"))
      (node (ref "D1") (pin "Y29") (pinfunction "VCCO_12_Y29") (pintype "power_in"))
    )
  )
)
